# MJ_AT6558-1613_V1_0.net
KiCad netlist of a schematic drawn in Altium Designer
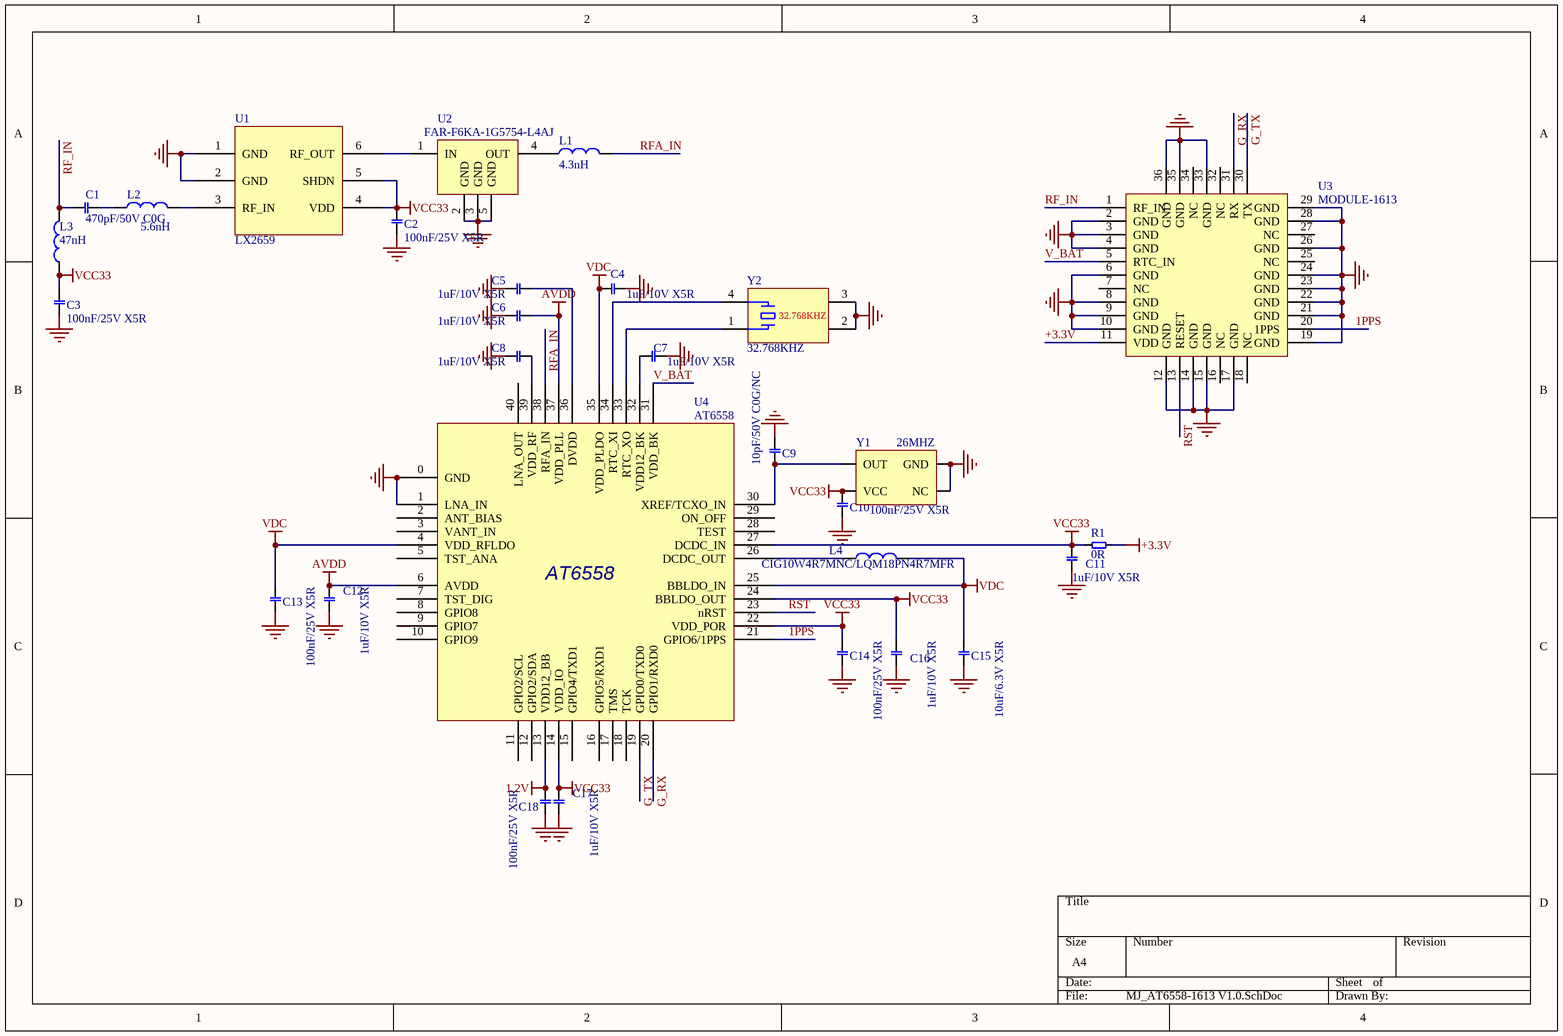
[diagram p0: MJ_AT6558-1613 V1.0.SchDoc]

(export (version "E")
  (design (tool "Eeschema 10.0.6"))
  (components
    (comp (ref "C1") (value "470pF/50V C0G") (footprint "0402") (libsource (lib "*") (part "CB")))
    (comp (ref "C2") (value "100nF/25V X5R") (footprint "0402") (libsource (lib "MY") (part "CB")))
    (comp (ref "C3") (value "100nF/25V X5R") (footprint "0402") (libsource (lib "MY") (part "CB")))
    (comp (ref "C4") (value "1uF/10V X5R") (footprint "0402") (libsource (lib "MY") (part "CB")))
    (comp (ref "C5") (value "1uF/10V X5R") (footprint "0402") (libsource (lib "MY") (part "CB")))
    (comp (ref "C6") (value "1uF/10V X5R") (footprint "0402") (libsource (lib "MY") (part "CB")))
    (comp (ref "C7") (value "1uF/10V X5R") (footprint "0402") (libsource (lib "MY") (part "CB")))
    (comp (ref "C8") (value "1uF/10V X5R") (footprint "0402") (libsource (lib "MY") (part "CB")))
    (comp (ref "C9") (value "10pF/50V C0G/NC") (footprint "0402") (libsource (lib "*") (part "CB")))
    (comp (ref "C10") (value "100nF/25V X5R") (footprint "0402") (libsource (lib "MY") (part "CB")))
    (comp (ref "C11") (value "1uF/10V X5R") (footprint "0402") (libsource (lib "MY") (part "CB")))
    (comp (ref "C12") (value "1uF/10V X5R") (footprint "0402") (libsource (lib "MY") (part "CB")))
    (comp (ref "C13") (value "100nF/25V X5R") (footprint "0402") (libsource (lib "MY") (part "CB")))
    (comp (ref "C14") (value "100nF/25V X5R") (footprint "0402") (libsource (lib "MY") (part "CB")))
    (comp (ref "C15") (value "10uF/6.3V X5R") (footprint "0603") (libsource (lib "MY") (part "CB")))
    (comp (ref "C16") (value "1uF/10V X5R") (footprint "0402") (libsource (lib "MY") (part "CB")))
    (comp (ref "C17") (value "1uF/10V X5R") (footprint "0402") (libsource (lib "MY") (part "CB")))
    (comp (ref "C18") (value "100nF/25V X5R") (footprint "0402") (libsource (lib "MY") (part "CB")))
    (comp (ref "L1") (value "4.3nH") (footprint "0402") (libsource (lib "") (part "L1_1")))
    (comp (ref "L2") (value "5.6nH") (footprint "0402") (libsource (lib "") (part "L1_1")))
    (comp (ref "L3") (value "47nH") (footprint "0402") (libsource (lib "*") (part "L1")))
    (comp (ref "L4")
      (value "CIG10W4R7MNC/LQM18PN4R7MFR")
      (footprint "0603")
      (description "SAMSUNG/MURATA")
      (libsource (lib "") (part "L1_1"))
    )
    (comp (ref "R1") (value "0R") (footprint "0402") (libsource (lib "MY") (part "R")))
    (comp (ref "U1") (value "LX2659") (footprint "dfn-6") (libsource (lib "MY") (part "LX2659")))
    (comp (ref "U2")
      (value "FAR-F6KA-1G5754-L4AJ")
      (footprint "s1365")
      (libsource (lib "MY") (part "SAW FILTER 1575"))
    )
    (comp (ref "U3")
      (value "MODULE-1613")
      (footprint "MODULE-1613")
      (libsource (lib "MY") (part "MODULE-1613"))
    )
    (comp (ref "U4")
      (value "AT6558")
      (footprint "AT6558")
      (description "AT6558 QFN40 5*5*0.8")
      (libsource (lib "MY") (part "AT6558"))
    )
    (comp (ref "Y1") (value "26MHZ") (footprint "JZ_TCXO2520") (libsource (lib "*") (part "XTAL")))
    (comp (ref "Y2") (value "32.768KHZ") (footprint "JZ-MC146") (libsource (lib "MY") (part "32.768KHZ")))
  )
  (nets
    (net (code "1") (name "+3.3V") (class "Default")
      (node (ref "R1") (pin "2") (pinfunction "2_2") (pintype "passive"))
      (node (ref "U3") (pin "11") (pinfunction "VDD_11") (pintype "passive"))
    )
    (net (code "2") (name "/1PPS") (class "Default")
      (node (ref "U3") (pin "20") (pinfunction "1PPS_20") (pintype "passive"))
      (node (ref "U4") (pin "21") (pinfunction "GPIO6/1PPS_21") (pintype "passive"))
    )
    (net (code "3") (name "/G_RX") (class "Default")
      (node (ref "U3") (pin "31") (pinfunction "RX_31") (pintype "passive"))
      (node (ref "U4") (pin "20") (pinfunction "GPIO1/RXD0_20") (pintype "passive"))
    )
    (net (code "4") (name "/G_TX") (class "Default")
      (node (ref "U3") (pin "30") (pinfunction "TX_30") (pintype "passive"))
      (node (ref "U4") (pin "19") (pinfunction "GPIO0/TXD0_19") (pintype "passive"))
    )
    (net (code "5") (name "/RFA_IN") (class "Default")
      (node (ref "L1") (pin "1") (pintype "passive"))
      (node (ref "U4") (pin "38") (pinfunction "RFA_IN_38") (pintype "passive"))
    )
    (net (code "6") (name "/RF_IN") (class "Default")
      (node (ref "C1") (pin "1") (pintype "passive"))
      (node (ref "L3") (pin "1") (pintype "passive"))
      (node (ref "U3") (pin "1") (pinfunction "RF_IN_1") (pintype "passive"))
    )
    (net (code "7") (name "/RST") (class "Default")
      (node (ref "U3") (pin "13") (pinfunction "RESET_13") (pintype "passive"))
      (node (ref "U4") (pin "23") (pinfunction "nRST_23") (pintype "passive"))
    )
    (net (code "8") (name "/V_BAT") (class "Default")
      (node (ref "U3") (pin "5") (pinfunction "RTC_IN_5") (pintype "passive"))
      (node (ref "U4") (pin "31") (pinfunction "VDD_BK_31") (pintype "passive"))
    )
    (net (code "9") (name "1.2V") (class "Default")
      (node (ref "C18") (pin "1") (pintype "passive"))
      (node (ref "U4") (pin "13") (pinfunction "VDD12_BB_13") (pintype "passive"))
    )
    (net (code "10") (name "AVDD") (class "Default")
      (node (ref "C12") (pin "1") (pintype "passive"))
      (node (ref "C6") (pin "1") (pintype "passive"))
      (node (ref "U4") (pin "37") (pinfunction "VDD_PLL_37") (pintype "passive"))
      (node (ref "U4") (pin "6") (pinfunction "AVDD_6") (pintype "passive"))
    )
    (net (code "11") (name "GND") (class "Default")
      (node (ref "C10") (pin "2") (pintype "passive"))
      (node (ref "C11") (pin "1") (pintype "passive"))
      (node (ref "C12") (pin "2") (pintype "passive"))
      (node (ref "C13") (pin "2") (pintype "passive"))
      (node (ref "C14") (pin "2") (pintype "passive"))
      (node (ref "C15") (pin "1") (pintype "passive"))
      (node (ref "C16") (pin "1") (pintype "passive"))
      (node (ref "C17") (pin "2") (pintype "passive"))
      (node (ref "C18") (pin "2") (pintype "passive"))
      (node (ref "C2") (pin "2") (pintype "passive"))
      (node (ref "C3") (pin "1") (pintype "passive"))
      (node (ref "C4") (pin "2") (pintype "passive"))
      (node (ref "C5") (pin "1") (pintype "passive"))
      (node (ref "C6") (pin "2") (pintype "passive"))
      (node (ref "C7") (pin "2") (pintype "passive"))
      (node (ref "C8") (pin "1") (pintype "passive"))
      (node (ref "C9") (pin "2") (pintype "passive"))
      (node (ref "U1") (pin "1") (pinfunction "GND_1") (pintype "passive"))
      (node (ref "U1") (pin "2") (pinfunction "GND_2") (pintype "passive"))
      (node (ref "U2") (pin "2") (pinfunction "GND_2") (pintype "passive"))
      (node (ref "U2") (pin "3") (pinfunction "GND_3") (pintype "passive"))
      (node (ref "U2") (pin "5") (pinfunction "GND_5") (pintype "passive"))
      (node (ref "U3") (pin "10") (pinfunction "GND_10") (pintype "passive"))
      (node (ref "U3") (pin "12") (pinfunction "GND_12") (pintype "passive"))
      (node (ref "U3") (pin "14") (pinfunction "GND_14") (pintype "passive"))
      (node (ref "U3") (pin "15") (pinfunction "GND_15") (pintype "passive"))
      (node (ref "U3") (pin "17") (pinfunction "GND_17") (pintype "passive"))
      (node (ref "U3") (pin "19") (pinfunction "GND_19") (pintype "passive"))
      (node (ref "U3") (pin "2") (pinfunction "GND_2") (pintype "passive"))
      (node (ref "U3") (pin "21") (pinfunction "GND_21") (pintype "passive"))
      (node (ref "U3") (pin "22") (pinfunction "GND_22") (pintype "passive"))
      (node (ref "U3") (pin "23") (pinfunction "GND_23") (pintype "passive"))
      (node (ref "U3") (pin "24") (pinfunction "GND_24") (pintype "passive"))
      (node (ref "U3") (pin "26") (pinfunction "GND_26") (pintype "passive"))
      (node (ref "U3") (pin "28") (pinfunction "GND_28") (pintype "passive"))
      (node (ref "U3") (pin "29") (pinfunction "GND_29") (pintype "passive"))
      (node (ref "U3") (pin "3") (pinfunction "GND_3") (pintype "passive"))
      (node (ref "U3") (pin "33") (pinfunction "GND_33") (pintype "passive"))
      (node (ref "U3") (pin "35") (pinfunction "GND_35") (pintype "passive"))
      (node (ref "U3") (pin "36") (pinfunction "GND_36") (pintype "passive"))
      (node (ref "U3") (pin "4") (pinfunction "GND_4") (pintype "passive"))
      (node (ref "U3") (pin "6") (pinfunction "GND_6") (pintype "passive"))
      (node (ref "U3") (pin "8") (pinfunction "GND_8") (pintype "passive"))
      (node (ref "U3") (pin "9") (pinfunction "GND_9") (pintype "passive"))
      (node (ref "U4") (pin "0") (pinfunction "GND_0") (pintype "passive"))
      (node (ref "U4") (pin "1") (pinfunction "LNA_IN_1") (pintype "passive"))
      (node (ref "Y1") (pin "1") (pinfunction "NC_1") (pintype "passive"))
      (node (ref "Y1") (pin "2") (pinfunction "GND_2") (pintype "passive"))
      (node (ref "Y2") (pin "2") (pinfunction "2_2") (pintype "passive"))
      (node (ref "Y2") (pin "3") (pinfunction "3_3") (pintype "passive"))
    )
    (net (code "12") (name "Net-(C1-Pad2)") (class "Default")
      (node (ref "C1") (pin "2") (pintype "passive"))
      (node (ref "L2") (pin "2") (pintype "passive"))
    )
    (net (code "13") (name "Net-(U1-RF_IN)") (class "Default")
      (node (ref "L2") (pin "1") (pintype "passive"))
      (node (ref "U1") (pin "3") (pinfunction "RF_IN_3") (pintype "passive"))
    )
    (net (code "14") (name "Net-(U1-RF_OUT)") (class "Default")
      (node (ref "U1") (pin "6") (pinfunction "RF_OUT_6") (pintype "passive"))
      (node (ref "U2") (pin "1") (pinfunction "IN_1") (pintype "passive"))
    )
    (net (code "15") (name "Net-(U2-OUT)") (class "Default")
      (node (ref "L1") (pin "2") (pintype "passive"))
      (node (ref "U2") (pin "4") (pinfunction "OUT_4") (pintype "passive"))
    )
    (net (code "16") (name "Net-(U4-DCDC_OUT)") (class "Default")
      (node (ref "L4") (pin "2") (pintype "passive"))
      (node (ref "U4") (pin "26") (pinfunction "DCDC_OUT_26") (pintype "passive"))
    )
    (net (code "17") (name "Net-(U4-DVDD)") (class "Default")
      (node (ref "C5") (pin "2") (pintype "passive"))
      (node (ref "U4") (pin "36") (pinfunction "DVDD_36") (pintype "passive"))
    )
    (net (code "18") (name "Net-(U4-RTC_XI)") (class "Default")
      (node (ref "U4") (pin "34") (pinfunction "RTC_XI_34") (pintype "passive"))
      (node (ref "Y2") (pin "4") (pinfunction "4_4") (pintype "passive"))
    )
    (net (code "19") (name "Net-(U4-RTC_XO)") (class "Default")
      (node (ref "U4") (pin "33") (pinfunction "RTC_XO_33") (pintype "passive"))
      (node (ref "Y2") (pin "1") (pinfunction "1_1") (pintype "passive"))
    )
    (net (code "20") (name "Net-(U4-VDD12_BK)") (class "Default")
      (node (ref "C7") (pin "1") (pintype "passive"))
      (node (ref "U4") (pin "32") (pinfunction "VDD12_BK_32") (pintype "passive"))
    )
    (net (code "21") (name "Net-(U4-VDD_RF)") (class "Default")
      (node (ref "C8") (pin "2") (pintype "passive"))
      (node (ref "U4") (pin "39") (pinfunction "VDD_RF_39") (pintype "passive"))
    )
    (net (code "22") (name "Net-(U4-XREF{slash}TCXO_IN)") (class "Default")
      (node (ref "C9") (pin "1") (pintype "passive"))
      (node (ref "U4") (pin "30") (pinfunction "XREF/TCXO_IN_30") (pintype "passive"))
      (node (ref "Y1") (pin "3") (pinfunction "OUT_3") (pintype "passive"))
    )
    (net (code "23") (name "VCC33") (class "Default")
      (node (ref "C10") (pin "1") (pintype "passive"))
      (node (ref "C11") (pin "2") (pintype "passive"))
      (node (ref "C14") (pin "1") (pintype "passive"))
      (node (ref "C16") (pin "2") (pintype "passive"))
      (node (ref "C17") (pin "1") (pintype "passive"))
      (node (ref "C2") (pin "1") (pintype "passive"))
      (node (ref "C3") (pin "2") (pintype "passive"))
      (node (ref "L3") (pin "2") (pintype "passive"))
      (node (ref "R1") (pin "1") (pinfunction "1_1") (pintype "passive"))
      (node (ref "U1") (pin "4") (pinfunction "VDD_4") (pintype "passive"))
      (node (ref "U1") (pin "5") (pinfunction "SHDN_5") (pintype "passive"))
      (node (ref "U4") (pin "14") (pinfunction "VDD_IO_14") (pintype "passive"))
      (node (ref "U4") (pin "22") (pinfunction "VDD_POR_22") (pintype "passive"))
      (node (ref "U4") (pin "24") (pinfunction "BBLDO_OUT_24") (pintype "passive"))
      (node (ref "U4") (pin "27") (pinfunction "DCDC_IN_27") (pintype "passive"))
      (node (ref "Y1") (pin "4") (pinfunction "VCC_4") (pintype "passive"))
    )
    (net (code "24") (name "VDC") (class "Default")
      (node (ref "C13") (pin "1") (pintype "passive"))
      (node (ref "C15") (pin "2") (pintype "passive"))
      (node (ref "C4") (pin "1") (pintype "passive"))
      (node (ref "L4") (pin "1") (pintype "passive"))
      (node (ref "U4") (pin "25") (pinfunction "BBLDO_IN_25") (pintype "passive"))
      (node (ref "U4") (pin "35") (pinfunction "VDD_PLDO_35") (pintype "passive"))
      (node (ref "U4") (pin "4") (pinfunction "VDD_RFLDO_4") (pintype "passive"))
    )
    (net (code "25") (name "unconnected-(U3-NC-Pad7)") (class "Default")
      (node (ref "U3") (pin "7") (pinfunction "NC_7") (pintype "passive"))
    )
    (net (code "26") (name "unconnected-(U3-NC-Pad16)") (class "Default")
      (node (ref "U3") (pin "16") (pinfunction "NC_16") (pintype "passive"))
    )
    (net (code "27") (name "unconnected-(U3-NC-Pad18)") (class "Default")
      (node (ref "U3") (pin "18") (pinfunction "NC_18") (pintype "passive"))
    )
    (net (code "28") (name "unconnected-(U3-NC-Pad25)") (class "Default")
      (node (ref "U3") (pin "25") (pinfunction "NC_25") (pintype "passive"))
    )
    (net (code "29") (name "unconnected-(U3-NC-Pad27)") (class "Default")
      (node (ref "U3") (pin "27") (pinfunction "NC_27") (pintype "passive"))
    )
    (net (code "30") (name "unconnected-(U3-NC-Pad32)") (class "Default")
      (node (ref "U3") (pin "32") (pinfunction "NC_32") (pintype "passive"))
    )
    (net (code "31") (name "unconnected-(U3-NC-Pad34)") (class "Default")
      (node (ref "U3") (pin "34") (pinfunction "NC_34") (pintype "passive"))
    )
    (net (code "32") (name "unconnected-(U4-ANT_BIAS-Pad2)") (class "Default")
      (node (ref "U4") (pin "2") (pinfunction "ANT_BIAS_2") (pintype "passive"))
    )
    (net (code "33") (name "unconnected-(U4-GPIO2{slash}SCL-Pad11)") (class "Default")
      (node (ref "U4") (pin "11") (pinfunction "GPIO2/SCL_11") (pintype "passive"))
    )
    (net (code "34") (name "unconnected-(U4-GPIO2{slash}SDA-Pad12)") (class "Default")
      (node (ref "U4") (pin "12") (pinfunction "GPIO2/SDA_12") (pintype "passive"))
    )
    (net (code "35") (name "unconnected-(U4-GPIO4{slash}TXD1-Pad15)") (class "Default")
      (node (ref "U4") (pin "15") (pinfunction "GPIO4/TXD1_15") (pintype "passive"))
    )
    (net (code "36") (name "unconnected-(U4-GPIO5{slash}RXD1-Pad16)") (class "Default")
      (node (ref "U4") (pin "16") (pinfunction "GPIO5/RXD1_16") (pintype "passive"))
    )
    (net (code "37") (name "unconnected-(U4-GPIO7-Pad9)") (class "Default")
      (node (ref "U4") (pin "9") (pinfunction "GPIO7_9") (pintype "passive"))
    )
    (net (code "38") (name "unconnected-(U4-GPIO8-Pad8)") (class "Default")
      (node (ref "U4") (pin "8") (pinfunction "GPIO8_8") (pintype "passive"))
    )
    (net (code "39") (name "unconnected-(U4-GPIO9-Pad10)") (class "Default")
      (node (ref "U4") (pin "10") (pinfunction "GPIO9_10") (pintype "passive"))
    )
    (net (code "40") (name "unconnected-(U4-LNA_OUT-Pad40)") (class "Default")
      (node (ref "U4") (pin "40") (pinfunction "LNA_OUT_40") (pintype "passive"))
    )
    (net (code "41") (name "unconnected-(U4-ON_OFF-Pad29)") (class "Default")
      (node (ref "U4") (pin "29") (pinfunction "ON_OFF_29") (pintype "passive"))
    )
    (net (code "42") (name "unconnected-(U4-TCK-Pad18)") (class "Default")
      (node (ref "U4") (pin "18") (pinfunction "TCK_18") (pintype "passive"))
    )
    (net (code "43") (name "unconnected-(U4-TEST-Pad28)") (class "Default")
      (node (ref "U4") (pin "28") (pinfunction "TEST_28") (pintype "passive"))
    )
    (net (code "44") (name "unconnected-(U4-TMS-Pad17)") (class "Default")
      (node (ref "U4") (pin "17") (pinfunction "TMS_17") (pintype "passive"))
    )
    (net (code "45") (name "unconnected-(U4-TST_ANA-Pad5)") (class "Default")
      (node (ref "U4") (pin "5") (pinfunction "TST_ANA_5") (pintype "passive"))
    )
    (net (code "46") (name "unconnected-(U4-TST_DIG-Pad7)") (class "Default")
      (node (ref "U4") (pin "7") (pinfunction "TST_DIG_7") (pintype "passive"))
    )
    (net (code "47") (name "unconnected-(U4-VANT_IN-Pad3)") (class "Default")
      (node (ref "U4") (pin "3") (pinfunction "VANT_IN_3") (pintype "passive"))
    )
  )
)
